# gokart_top.net
KiCad netlist of a schematic drawn in Altium Designer
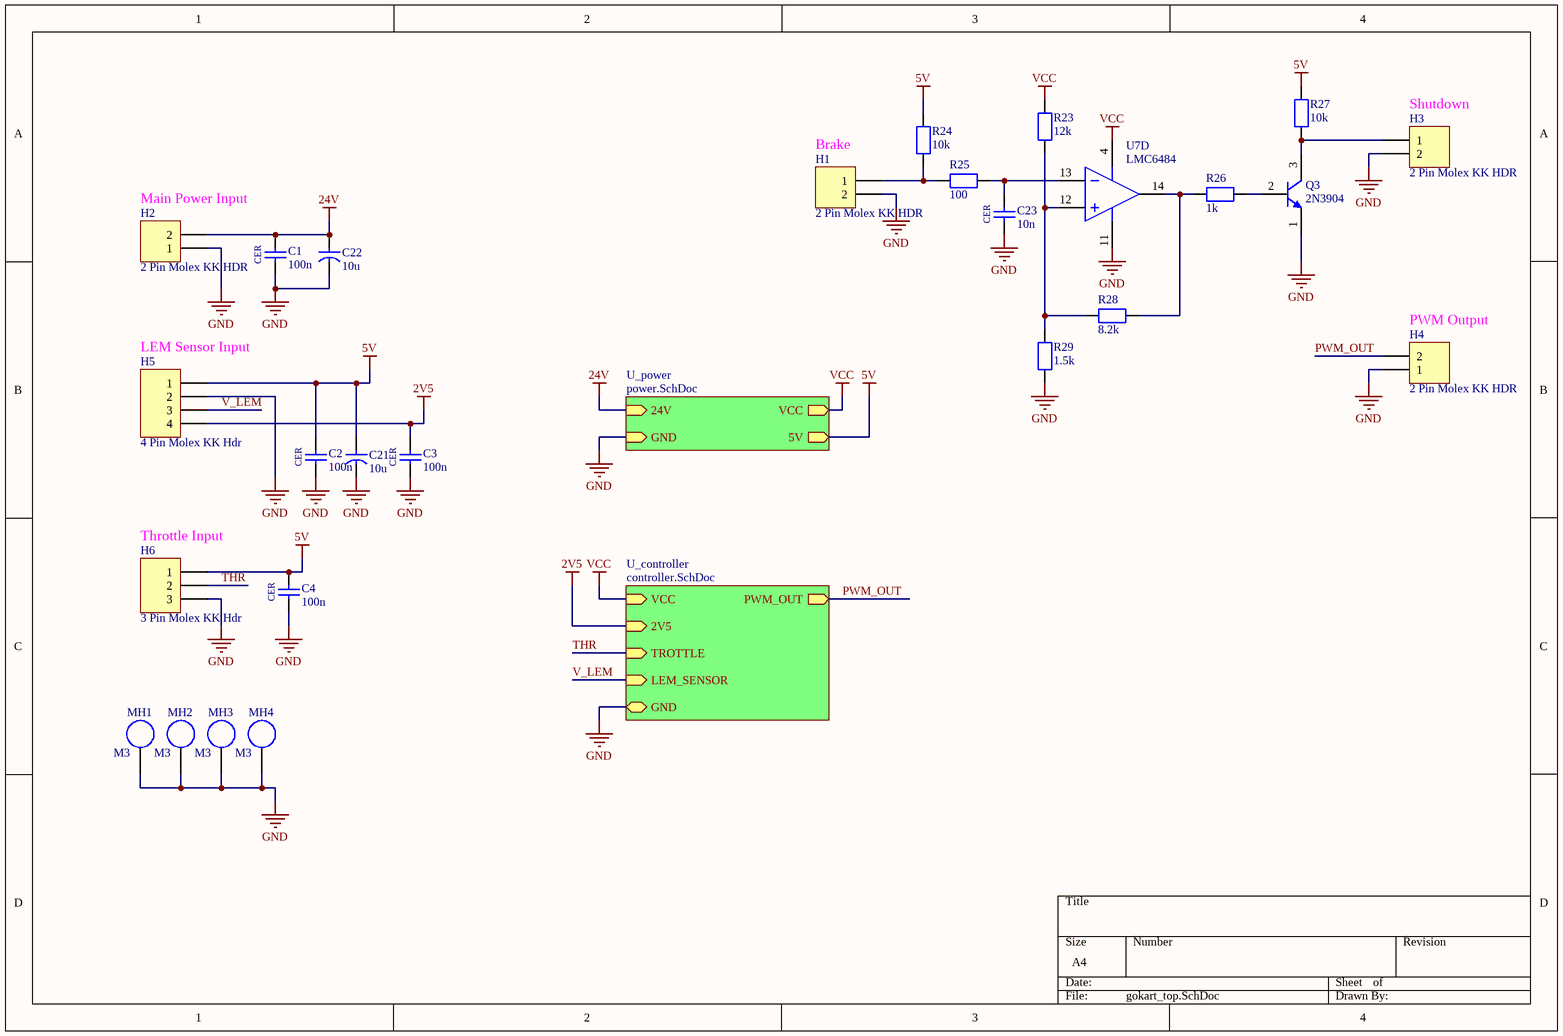
[diagram p0: gokart_top.SchDoc]

(export (version "E")
  (design (tool "Eeschema 10.0.6"))
  (components
    (comp (ref "C1") (value "100n") (footprint "CAP_CER_2.50") (libsource (lib "go_kart") (part "CAP_CER")))
    (comp (ref "C2") (value "100n") (footprint "CAP_CER_2.50") (libsource (lib "go_kart") (part "CAP_CER")))
    (comp (ref "C3") (value "100n") (footprint "CAP_CER_2.50") (libsource (lib "go_kart") (part "CAP_CER")))
    (comp (ref "C4") (value "100n") (footprint "CAP_CER_2.50") (libsource (lib "go_kart") (part "CAP_CER")))
    (comp (ref "C21") (value "10u") (footprint "CAP_ELEC_2.50") (libsource (lib "go_kart") (part "CAP_ELEC")))
    (comp (ref "C22") (value "10u") (footprint "CAP_ELEC_2.50") (libsource (lib "go_kart") (part "CAP_ELEC")))
    (comp (ref "C23") (value "10n") (footprint "CAP_CER_2.50") (libsource (lib "go_kart") (part "CAP_CER")))
    (comp (ref "H1")
      (value "2 Pin Molex KK HDR")
      (footprint "MOLEX_KK_2_HDR")
      (description "CONN HEADER 2POS 2.54mm VERT_Thru Hole")
      (libsource (lib "") (part "JA_MOLEX_KK_2POS_3"))
    )
    (comp (ref "H2")
      (value "2 Pin Molex KK HDR")
      (footprint "MOLEX_KK_2_HDR")
      (description "CONN HEADER 2POS 2.54mm VERT_Thru Hole")
      (libsource (lib "ECE AD19Components_19V1") (part "JA_MOLEX_KK_2POS"))
    )
    (comp (ref "H3")
      (value "2 Pin Molex KK HDR")
      (footprint "MOLEX_KK_2_HDR")
      (description "CONN HEADER 2POS 2.54mm VERT_Thru Hole")
      (libsource (lib "") (part "JA_MOLEX_KK_2POS_2"))
    )
    (comp (ref "H4")
      (value "2 Pin Molex KK HDR")
      (footprint "MOLEX_KK_2_HDR")
      (description "CONN HEADER 2POS 2.54mm VERT_Thru Hole")
      (libsource (lib "") (part "JA_MOLEX_KK_2POS_1"))
    )
    (comp (ref "H5")
      (value "4 Pin Molex KK Hdr")
      (footprint "MOLEX_KK_4_HDR")
      (description "CONN HEADER 4POS 2.54mm VERT_Thru Hole")
      (fields (field (name "MANUFACTURER") "Molex"))
      (libsource (lib "ECE AD19Components_19V1") (part "JA_MOLEX_KK_4POS"))
    )
    (comp (ref "H6")
      (value "3 Pin Molex KK Hdr")
      (footprint "MOLEX_KK_3_HDR")
      (description "CONN HEADER 3POS 2.54mm VERT_Thru Hole")
      (fields (field (name "MANUFACTURER") "Molex"))
      (libsource (lib "ECE AD19Components_19V1") (part "JA_MOLEX_KK_3POS"))
    )
    (comp (ref "MH1")
      (value "M3")
      (footprint "M3-Mounting-Hole")
      (libsource (lib "go_kart") (part "M3-Mounting-Hole"))
    )
    (comp (ref "MH2")
      (value "M3")
      (footprint "M3-Mounting-Hole")
      (libsource (lib "go_kart") (part "M3-Mounting-Hole"))
    )
    (comp (ref "MH3")
      (value "M3")
      (footprint "M3-Mounting-Hole")
      (libsource (lib "go_kart") (part "M3-Mounting-Hole"))
    )
    (comp (ref "MH4")
      (value "M3")
      (footprint "M3-Mounting-Hole")
      (libsource (lib "go_kart") (part "M3-Mounting-Hole"))
    )
    (comp (ref "Q3")
      (value "2N3904")
      (footprint "ONSC-TO-92-3-29-04_AD")
      (libsource (lib "go_kart") (part "2N3904"))
    )
    (comp (ref "R23")
      (value "12k")
      (footprint "RESISTOR_THROUGH_HOLE")
      (libsource (lib "go_kart") (part "Resistor"))
    )
    (comp (ref "R24")
      (value "10k")
      (footprint "RESISTOR_THROUGH_HOLE")
      (libsource (lib "go_kart") (part "Resistor"))
    )
    (comp (ref "R25")
      (value "100")
      (footprint "RESISTOR_THROUGH_HOLE")
      (libsource (lib "go_kart") (part "Resistor"))
    )
    (comp (ref "R26")
      (value "1k")
      (footprint "RESISTOR_THROUGH_HOLE")
      (libsource (lib "go_kart") (part "Resistor"))
    )
    (comp (ref "R27")
      (value "10k")
      (footprint "RESISTOR_THROUGH_HOLE")
      (libsource (lib "go_kart") (part "Resistor"))
    )
    (comp (ref "R28")
      (value "8.2k")
      (footprint "RESISTOR_THROUGH_HOLE")
      (libsource (lib "go_kart") (part "Resistor"))
    )
    (comp (ref "R29")
      (value "1.5k")
      (footprint "RESISTOR_THROUGH_HOLE")
      (libsource (lib "go_kart") (part "Resistor"))
    )
    (comp (ref "U7") (value "LMC6484") (footprint "TI-J14") (libsource (lib "go_kart") (part "LMC6484")))
  )
  (nets
    (net (code "1") (name "/PWM_OUT") (class "Default")
      (node (ref "H4") (pin "2") (pinfunction "2_2") (pintype "passive"))
    )
    (net (code "2") (name "/THR") (class "Default")
      (node (ref "H6") (pin "2") (pinfunction "2_2") (pintype "passive"))
    )
    (net (code "3") (name "/V_LEM") (class "Default")
      (node (ref "H5") (pin "3") (pinfunction "3_3") (pintype "passive"))
    )
    (net (code "4") (name "2V5") (class "Default")
      (node (ref "C3") (pin "2") (pinfunction "2_2") (pintype "passive"))
      (node (ref "H5") (pin "4") (pinfunction "4_4") (pintype "passive"))
    )
    (net (code "5") (name "5V") (class "Default")
      (node (ref "C2") (pin "2") (pinfunction "2_2") (pintype "passive"))
      (node (ref "C21") (pin "1") (pinfunction "1_1") (pintype "passive"))
      (node (ref "C4") (pin "2") (pinfunction "2_2") (pintype "passive"))
      (node (ref "H5") (pin "1") (pinfunction "1_1") (pintype "passive"))
      (node (ref "H6") (pin "1") (pinfunction "1_1") (pintype "passive"))
      (node (ref "R24") (pin "2") (pinfunction "2_2") (pintype "passive"))
      (node (ref "R27") (pin "2") (pinfunction "2_2") (pintype "passive"))
    )
    (net (code "6") (name "24V") (class "Default")
      (node (ref "C1") (pin "2") (pinfunction "2_2") (pintype "passive"))
      (node (ref "C22") (pin "1") (pinfunction "1_1") (pintype "passive"))
      (node (ref "H2") (pin "2") (pinfunction "2_2") (pintype "passive"))
    )
    (net (code "7") (name "GND") (class "Default")
      (node (ref "C1") (pin "1") (pinfunction "1_1") (pintype "passive"))
      (node (ref "C2") (pin "1") (pinfunction "1_1") (pintype "passive"))
      (node (ref "C21") (pin "2") (pinfunction "2_2") (pintype "passive"))
      (node (ref "C22") (pin "2") (pinfunction "2_2") (pintype "passive"))
      (node (ref "C23") (pin "1") (pinfunction "1_1") (pintype "passive"))
      (node (ref "C3") (pin "1") (pinfunction "1_1") (pintype "passive"))
      (node (ref "C4") (pin "1") (pinfunction "1_1") (pintype "passive"))
      (node (ref "H1") (pin "2") (pinfunction "2_2") (pintype "passive"))
      (node (ref "H2") (pin "1") (pinfunction "1_1") (pintype "passive"))
      (node (ref "H3") (pin "2") (pinfunction "2_2") (pintype "passive"))
      (node (ref "H4") (pin "1") (pinfunction "1_1") (pintype "passive"))
      (node (ref "H5") (pin "2") (pinfunction "2_2") (pintype "passive"))
      (node (ref "H6") (pin "3") (pinfunction "3_3") (pintype "passive"))
      (node (ref "MH1") (pin "1") (pinfunction "1_1") (pintype "passive"))
      (node (ref "MH2") (pin "1") (pinfunction "1_1") (pintype "passive"))
      (node (ref "MH3") (pin "1") (pinfunction "1_1") (pintype "passive"))
      (node (ref "MH4") (pin "1") (pinfunction "1_1") (pintype "passive"))
      (node (ref "Q3") (pin "1") (pinfunction "E_1") (pintype "passive"))
      (node (ref "R29") (pin "1") (pinfunction "1_1") (pintype "passive"))
      (node (ref "U7") (pin "11") (pinfunction "VCC-_11") (pintype "passive"))
    )
    (net (code "8") (name "Net-(H1-Pad1)") (class "Default")
      (node (ref "H1") (pin "1") (pinfunction "1_1") (pintype "passive"))
      (node (ref "R24") (pin "1") (pinfunction "1_1") (pintype "passive"))
      (node (ref "R25") (pin "1") (pinfunction "1_1") (pintype "passive"))
    )
    (net (code "9") (name "Net-(Q3-B)") (class "Default")
      (node (ref "Q3") (pin "2") (pinfunction "B_2") (pintype "passive"))
      (node (ref "R26") (pin "1") (pinfunction "1_1") (pintype "passive"))
    )
    (net (code "10") (name "Net-(Q3-C)") (class "Default")
      (node (ref "H3") (pin "1") (pinfunction "1_1") (pintype "passive"))
      (node (ref "Q3") (pin "3") (pinfunction "C_3") (pintype "passive"))
      (node (ref "R27") (pin "1") (pinfunction "1_1") (pintype "passive"))
    )
    (net (code "11") (name "Net-(U7D-IN4+)") (class "Default")
      (node (ref "R23") (pin "1") (pinfunction "1_1") (pintype "passive"))
      (node (ref "R28") (pin "1") (pinfunction "1_1") (pintype "passive"))
      (node (ref "R29") (pin "2") (pinfunction "2_2") (pintype "passive"))
      (node (ref "U7") (pin "12") (pinfunction "IN4+_12") (pintype "passive"))
    )
    (net (code "12") (name "Net-(U7D-IN4-)") (class "Default")
      (node (ref "C23") (pin "2") (pinfunction "2_2") (pintype "passive"))
      (node (ref "R25") (pin "2") (pinfunction "2_2") (pintype "passive"))
      (node (ref "U7") (pin "13") (pinfunction "IN4-_13") (pintype "passive"))
    )
    (net (code "13") (name "Net-(U7D-OUT4)") (class "Default")
      (node (ref "R26") (pin "2") (pinfunction "2_2") (pintype "passive"))
      (node (ref "R28") (pin "2") (pinfunction "2_2") (pintype "passive"))
      (node (ref "U7") (pin "14") (pinfunction "OUT4_14") (pintype "passive"))
    )
    (net (code "14") (name "VCC") (class "Default")
      (node (ref "R23") (pin "2") (pinfunction "2_2") (pintype "passive"))
      (node (ref "U7") (pin "4") (pinfunction "VCC+_4") (pintype "passive"))
    )
  )
)
